# 06_SOM.net
KiCad netlist of a schematic drawn in Altium Designer
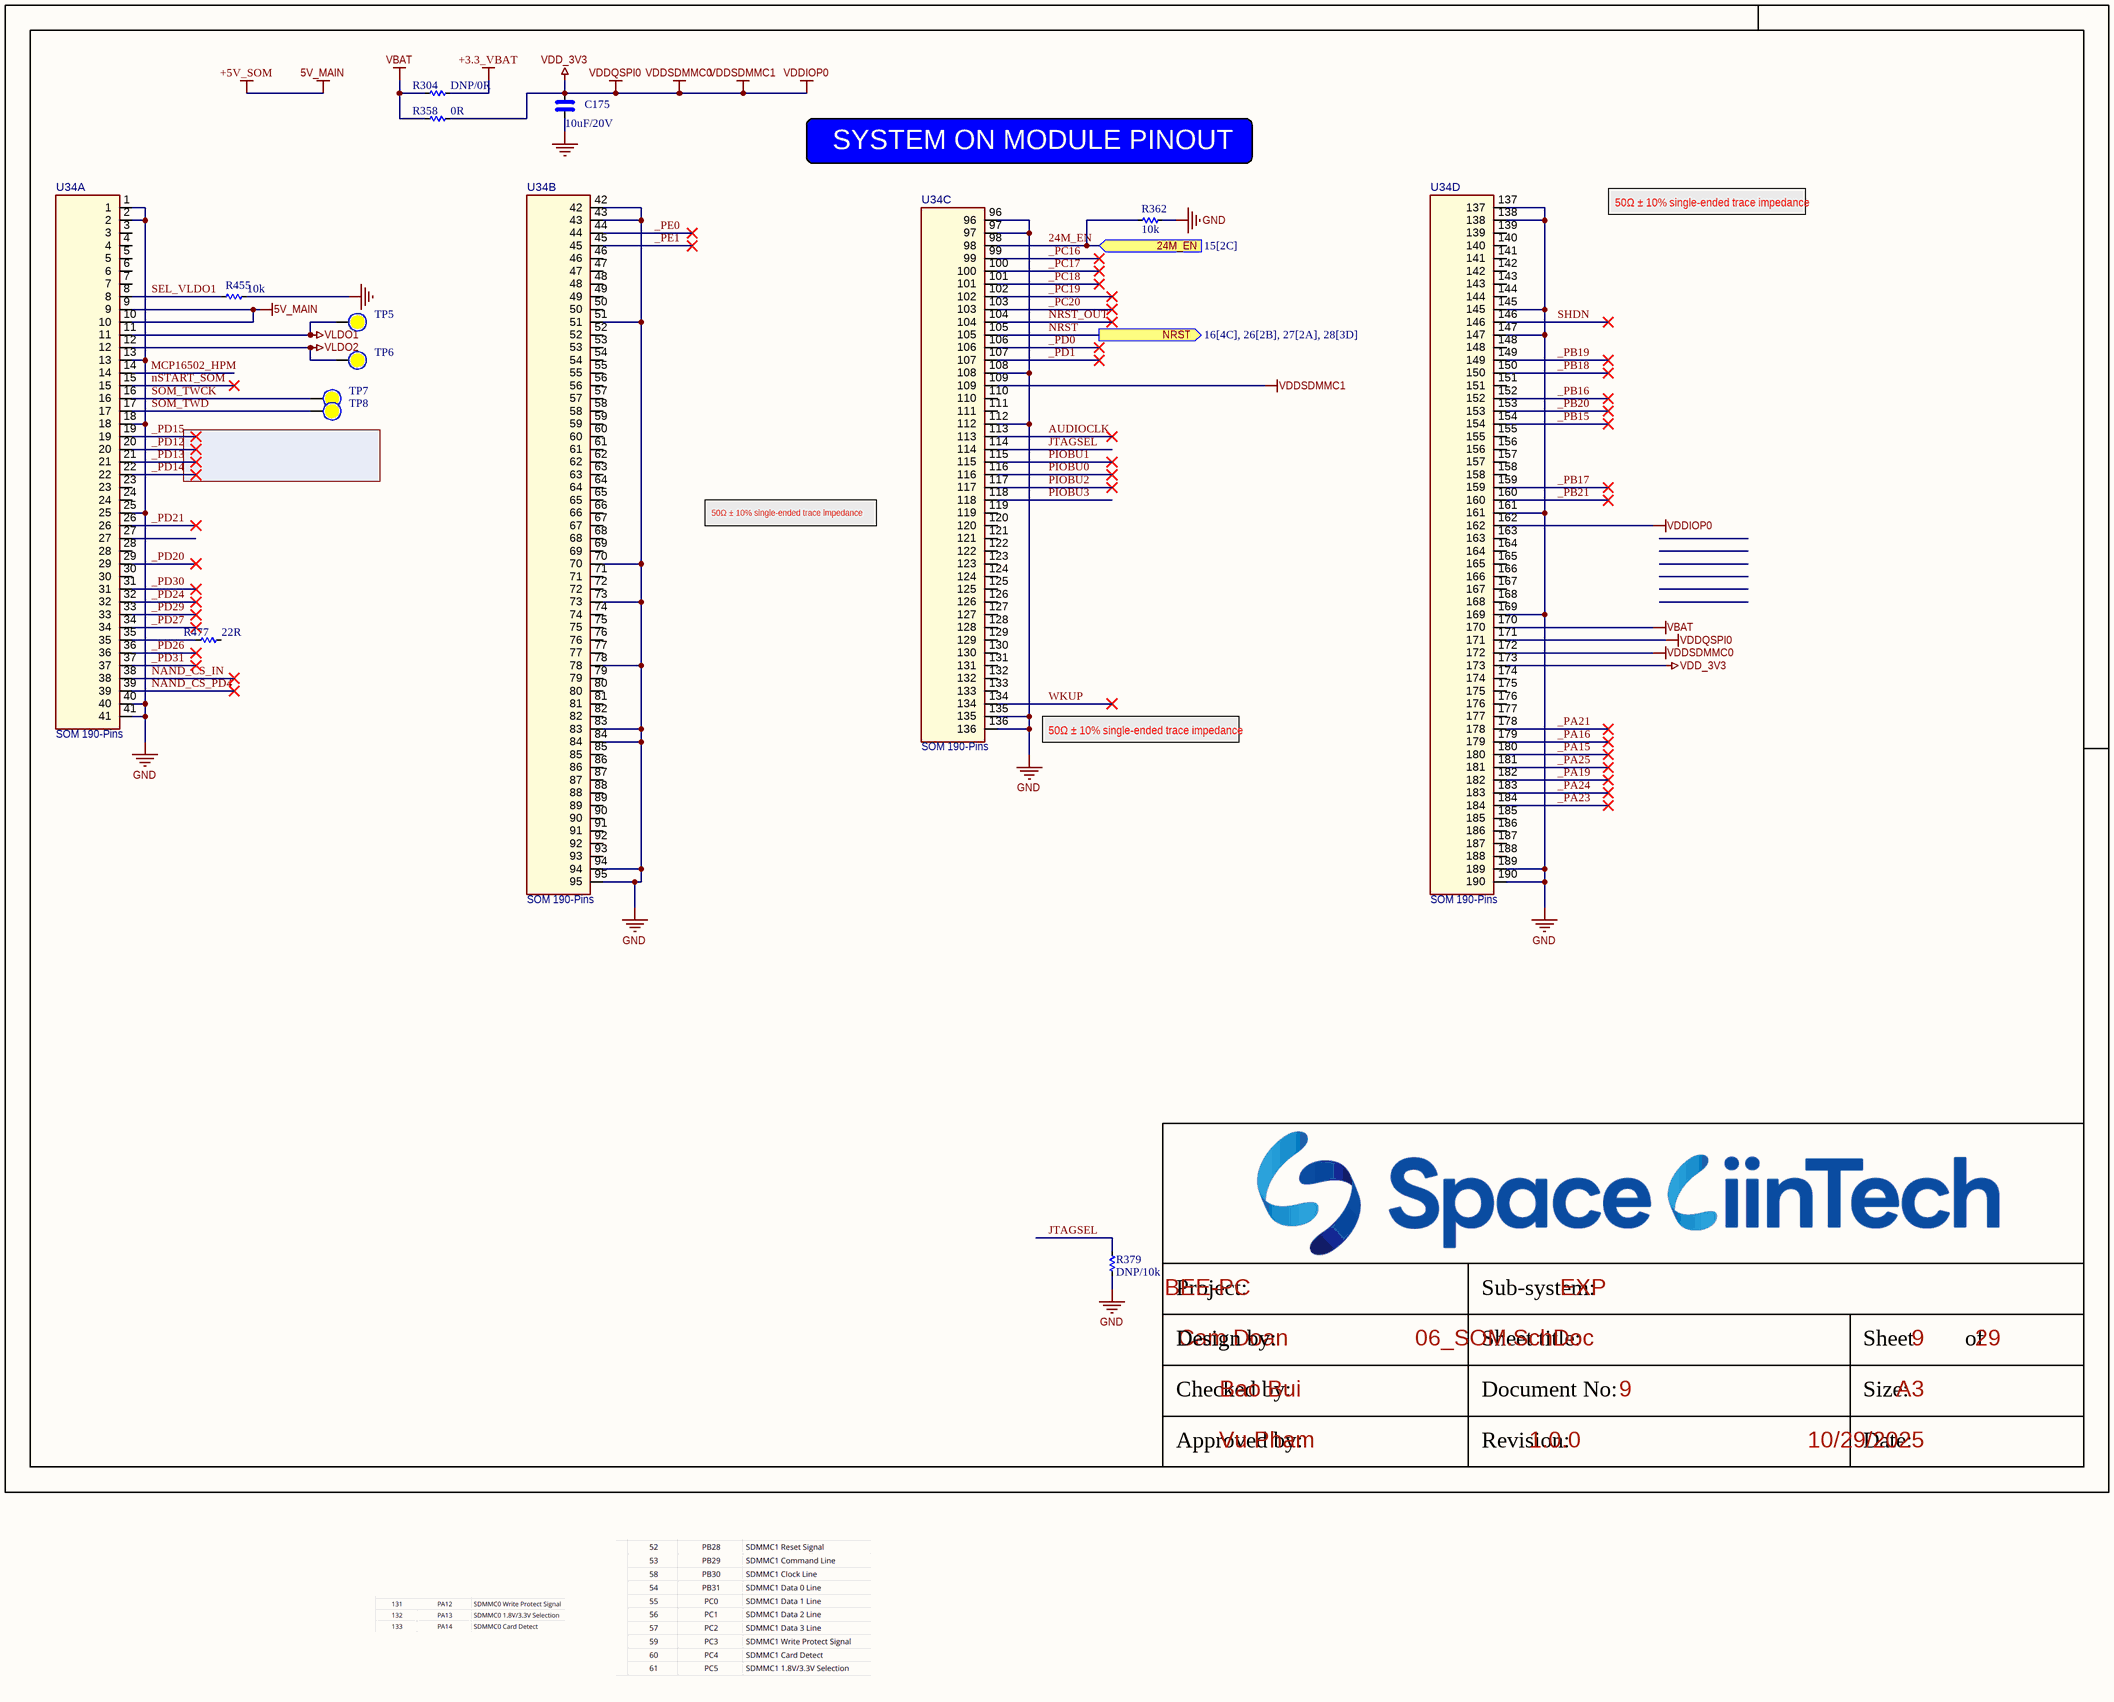
[diagram p0: 06_SOM.SchDoc]

(export (version "E")
  (design (tool "Eeschema 10.0.6"))
  (components
    (comp (ref "C175")
      (value "10uF/20V")
      (footprint "CAP_C_2012X110")
      (description "CAP CHIP High Value")
      (libsource (lib "LABLIB") (part "_CAP_C_High_2"))
    )
    (comp (ref "R304")
      (value "DNP/0R")
      (footprint "RES_C_1005X40")
      (description "RES")
      (libsource (lib "LABLIB") (part "_RES_B_2"))
    )
    (comp (ref "R358")
      (value "0R")
      (footprint "RES_C_1005X40")
      (description "RES")
      (libsource (lib "LABLIB") (part "_RES_B_2"))
    )
    (comp (ref "R362")
      (value "10k")
      (footprint "RES_C_1005X40")
      (description "RES")
      (libsource (lib "LABLIB") (part "_RES_B_2"))
    )
    (comp (ref "R379")
      (value "DNP/10k")
      (footprint "RES_C_1005X40")
      (description "RES")
      (libsource (lib "LABLIB") (part "_RES_B_2"))
    )
    (comp (ref "R455")
      (value "10k")
      (footprint "RES_C_1005X40")
      (description "RES")
      (libsource (lib "LABLIB") (part "_RES_B_2"))
    )
    (comp (ref "R477")
      (value "22R")
      (footprint "RES_C_1005X40")
      (description "RES")
      (libsource (lib "LABLIB") (part "_RES_B_2"))
    )
    (comp (ref "TP5")
      (value "~")
      (footprint "Testpoint_TH_D130H80")
      (description "Test Point")
      (libsource (lib "LABLIB") (part "Test Point"))
    )
    (comp (ref "TP6")
      (value "~")
      (footprint "Testpoint_TH_D130H80")
      (description "Test Point")
      (libsource (lib "LABLIB") (part "Test Point"))
    )
    (comp (ref "TP7")
      (value "~")
      (footprint "Testpoint_TH_D130H80")
      (description "Test Point")
      (libsource (lib "LABLIB") (part "Test Point"))
    )
    (comp (ref "TP8")
      (value "~")
      (footprint "Testpoint_TH_D130H80")
      (description "Test Point")
      (libsource (lib "LABLIB") (part "Test Point"))
    )
    (comp (ref "U34")
      (value "SOM 190-Pins")
      (footprint "SOM-38MMX30MM")
      (description "190-Castellated thru-holes, 38mm x 30mm package")
      (libsource (lib "SOM-190") (part "SOM-190"))
    )
  )
  (nets
    (net (code "1") (name "+3.3_VBAT") (class "Default")
      (node (ref "R304") (pin "1") (pinfunction "1_1") (pintype "passive"))
    )
    (net (code "2") (name "+5V_SOM") (class "Default")
      (node (ref "U34") (pin "10") (pinfunction "10_10") (pintype "passive"))
      (node (ref "U34") (pin "9") (pinfunction "9_9") (pintype "passive"))
    )
    (net (code "3") (name "/24M_EN") (class "Default")
      (node (ref "R362") (pin "2") (pinfunction "2_2") (pintype "passive"))
      (node (ref "U34") (pin "98") (pinfunction "98_98") (pintype "passive"))
    )
    (net (code "4") (name "/AUDIOCLK") (class "Default")
      (node (ref "U34") (pin "113") (pinfunction "113_113") (pintype "passive+no_connect"))
    )
    (net (code "5") (name "/JTAGSEL") (class "Default")
      (node (ref "R379") (pin "2") (pinfunction "2_2") (pintype "passive"))
      (node (ref "U34") (pin "114") (pinfunction "114_114") (pintype "passive"))
    )
    (net (code "6") (name "/MCP16502_HPM") (class "Default")
      (node (ref "U34") (pin "14") (pinfunction "14_14") (pintype "passive"))
    )
    (net (code "7") (name "/NAND_CS_IN") (class "Default")
      (node (ref "U34") (pin "38") (pinfunction "38_38") (pintype "passive+no_connect"))
    )
    (net (code "8") (name "/NAND_CS_PD4") (class "Default")
      (node (ref "U34") (pin "39") (pinfunction "39_39") (pintype "passive+no_connect"))
    )
    (net (code "9") (name "/NRST") (class "Default")
      (node (ref "U34") (pin "105") (pinfunction "105_105") (pintype "passive"))
    )
    (net (code "10") (name "/NRST_OUT") (class "Default")
      (node (ref "U34") (pin "104") (pinfunction "104_104") (pintype "passive+no_connect"))
    )
    (net (code "11") (name "/PIOBU0") (class "Default")
      (node (ref "U34") (pin "116") (pinfunction "116_116") (pintype "passive+no_connect"))
    )
    (net (code "12") (name "/PIOBU1") (class "Default")
      (node (ref "U34") (pin "115") (pinfunction "115_115") (pintype "passive+no_connect"))
    )
    (net (code "13") (name "/PIOBU2") (class "Default")
      (node (ref "U34") (pin "117") (pinfunction "117_117") (pintype "passive+no_connect"))
    )
    (net (code "14") (name "/PIOBU3") (class "Default")
      (node (ref "U34") (pin "118") (pinfunction "118_118") (pintype "passive"))
    )
    (net (code "15") (name "/SEL_VLDO1") (class "Default")
      (node (ref "R455") (pin "2") (pinfunction "2_2") (pintype "passive"))
      (node (ref "U34") (pin "8") (pinfunction "8_8") (pintype "passive"))
    )
    (net (code "16") (name "/SHDN") (class "Default")
      (node (ref "U34") (pin "146") (pinfunction "146_146") (pintype "passive+no_connect"))
    )
    (net (code "17") (name "/SOM_TWCK") (class "Default")
      (node (ref "TP7") (pin "0") (pinfunction "0_0") (pintype "passive"))
      (node (ref "U34") (pin "16") (pinfunction "16_16") (pintype "passive"))
    )
    (net (code "18") (name "/SOM_TWD") (class "Default")
      (node (ref "TP8") (pin "0") (pinfunction "0_0") (pintype "passive"))
      (node (ref "U34") (pin "17") (pinfunction "17_17") (pintype "passive"))
    )
    (net (code "19") (name "/WKUP") (class "Default")
      (node (ref "U34") (pin "134") (pinfunction "134_134") (pintype "passive+no_connect"))
    )
    (net (code "20") (name "/_PA15") (class "Default")
      (node (ref "U34") (pin "180") (pinfunction "180_180") (pintype "passive+no_connect"))
    )
    (net (code "21") (name "/_PA16") (class "Default")
      (node (ref "U34") (pin "179") (pinfunction "179_179") (pintype "passive+no_connect"))
    )
    (net (code "22") (name "/_PA19") (class "Default")
      (node (ref "U34") (pin "182") (pinfunction "182_182") (pintype "passive+no_connect"))
    )
    (net (code "23") (name "/_PA21") (class "Default")
      (node (ref "U34") (pin "178") (pinfunction "178_178") (pintype "passive+no_connect"))
    )
    (net (code "24") (name "/_PA23") (class "Default")
      (node (ref "U34") (pin "184") (pinfunction "184_184") (pintype "passive+no_connect"))
    )
    (net (code "25") (name "/_PA24") (class "Default")
      (node (ref "U34") (pin "183") (pinfunction "183_183") (pintype "passive+no_connect"))
    )
    (net (code "26") (name "/_PA25") (class "Default")
      (node (ref "U34") (pin "181") (pinfunction "181_181") (pintype "passive+no_connect"))
    )
    (net (code "27") (name "/_PB15") (class "Default")
      (node (ref "U34") (pin "154") (pinfunction "154_154") (pintype "passive+no_connect"))
    )
    (net (code "28") (name "/_PB16") (class "Default")
      (node (ref "U34") (pin "152") (pinfunction "152_152") (pintype "passive+no_connect"))
    )
    (net (code "29") (name "/_PB17") (class "Default")
      (node (ref "U34") (pin "159") (pinfunction "159_159") (pintype "passive+no_connect"))
    )
    (net (code "30") (name "/_PB18") (class "Default")
      (node (ref "U34") (pin "150") (pinfunction "150_150") (pintype "passive+no_connect"))
    )
    (net (code "31") (name "/_PB19") (class "Default")
      (node (ref "U34") (pin "149") (pinfunction "149_149") (pintype "passive+no_connect"))
    )
    (net (code "32") (name "/_PB20") (class "Default")
      (node (ref "U34") (pin "153") (pinfunction "153_153") (pintype "passive+no_connect"))
    )
    (net (code "33") (name "/_PB21") (class "Default")
      (node (ref "U34") (pin "160") (pinfunction "160_160") (pintype "passive+no_connect"))
    )
    (net (code "34") (name "/_PC16") (class "Default")
      (node (ref "U34") (pin "99") (pinfunction "99_99") (pintype "passive+no_connect"))
    )
    (net (code "35") (name "/_PC17") (class "Default")
      (node (ref "U34") (pin "100") (pinfunction "100_100") (pintype "passive+no_connect"))
    )
    (net (code "36") (name "/_PC18") (class "Default")
      (node (ref "U34") (pin "101") (pinfunction "101_101") (pintype "passive+no_connect"))
    )
    (net (code "37") (name "/_PC19") (class "Default")
      (node (ref "U34") (pin "102") (pinfunction "102_102") (pintype "passive+no_connect"))
    )
    (net (code "38") (name "/_PC20") (class "Default")
      (node (ref "U34") (pin "103") (pinfunction "103_103") (pintype "passive+no_connect"))
    )
    (net (code "39") (name "/_PD0") (class "Default")
      (node (ref "U34") (pin "106") (pinfunction "106_106") (pintype "passive+no_connect"))
    )
    (net (code "40") (name "/_PD1") (class "Default")
      (node (ref "U34") (pin "107") (pinfunction "107_107") (pintype "passive+no_connect"))
    )
    (net (code "41") (name "/_PD12") (class "Default")
      (node (ref "U34") (pin "20") (pinfunction "20_20") (pintype "passive+no_connect"))
    )
    (net (code "42") (name "/_PD13") (class "Default")
      (node (ref "U34") (pin "21") (pinfunction "21_21") (pintype "passive+no_connect"))
    )
    (net (code "43") (name "/_PD14") (class "Default")
      (node (ref "U34") (pin "22") (pinfunction "22_22") (pintype "passive+no_connect"))
    )
    (net (code "44") (name "/_PD15") (class "Default")
      (node (ref "U34") (pin "19") (pinfunction "19_19") (pintype "passive+no_connect"))
    )
    (net (code "45") (name "/_PD20") (class "Default")
      (node (ref "U34") (pin "29") (pinfunction "29_29") (pintype "passive+no_connect"))
    )
    (net (code "46") (name "/_PD21") (class "Default")
      (node (ref "U34") (pin "26") (pinfunction "26_26") (pintype "passive+no_connect"))
    )
    (net (code "47") (name "/_PD24") (class "Default")
      (node (ref "U34") (pin "32") (pinfunction "32_32") (pintype "passive+no_connect"))
    )
    (net (code "48") (name "/_PD26") (class "Default")
      (node (ref "U34") (pin "36") (pinfunction "36_36") (pintype "passive+no_connect"))
    )
    (net (code "49") (name "/_PD27") (class "Default")
      (node (ref "U34") (pin "34") (pinfunction "34_34") (pintype "passive+no_connect"))
    )
    (net (code "50") (name "/_PD29") (class "Default")
      (node (ref "U34") (pin "33") (pinfunction "33_33") (pintype "passive+no_connect"))
    )
    (net (code "51") (name "/_PD30") (class "Default")
      (node (ref "U34") (pin "31") (pinfunction "31_31") (pintype "passive+no_connect"))
    )
    (net (code "52") (name "/_PD31") (class "Default")
      (node (ref "U34") (pin "37") (pinfunction "37_37") (pintype "passive+no_connect"))
    )
    (net (code "53") (name "/_PE0") (class "Default")
      (node (ref "U34") (pin "44") (pinfunction "44_44") (pintype "passive+no_connect"))
    )
    (net (code "54") (name "/_PE1") (class "Default")
      (node (ref "U34") (pin "45") (pinfunction "45_45") (pintype "passive+no_connect"))
    )
    (net (code "55") (name "/nSTART_SOM") (class "Default")
      (node (ref "U34") (pin "15") (pinfunction "15_15") (pintype "passive+no_connect"))
    )
    (net (code "56") (name "GND") (class "Default")
      (node (ref "C175") (pin "2") (pinfunction "2_2") (pintype "passive"))
      (node (ref "R362") (pin "1") (pinfunction "1_1") (pintype "passive"))
      (node (ref "R379") (pin "1") (pinfunction "1_1") (pintype "passive"))
      (node (ref "R455") (pin "1") (pinfunction "1_1") (pintype "passive"))
      (node (ref "U34") (pin "1") (pinfunction "1_1") (pintype "passive"))
      (node (ref "U34") (pin "108") (pinfunction "108_108") (pintype "passive"))
      (node (ref "U34") (pin "112") (pinfunction "112_112") (pintype "passive"))
      (node (ref "U34") (pin "13") (pinfunction "13_13") (pintype "passive"))
      (node (ref "U34") (pin "135") (pinfunction "135_135") (pintype "passive"))
      (node (ref "U34") (pin "136") (pinfunction "136_136") (pintype "passive"))
      (node (ref "U34") (pin "137") (pinfunction "137_137") (pintype "passive"))
      (node (ref "U34") (pin "138") (pinfunction "138_138") (pintype "passive"))
      (node (ref "U34") (pin "145") (pinfunction "145_145") (pintype "passive"))
      (node (ref "U34") (pin "147") (pinfunction "147_147") (pintype "passive"))
      (node (ref "U34") (pin "161") (pinfunction "161_161") (pintype "passive"))
      (node (ref "U34") (pin "169") (pinfunction "169_169") (pintype "passive"))
      (node (ref "U34") (pin "18") (pinfunction "18_18") (pintype "passive"))
      (node (ref "U34") (pin "189") (pinfunction "189_189") (pintype "passive"))
      (node (ref "U34") (pin "190") (pinfunction "190_190") (pintype "passive"))
      (node (ref "U34") (pin "2") (pinfunction "2_2") (pintype "passive"))
      (node (ref "U34") (pin "25") (pinfunction "25_25") (pintype "passive"))
      (node (ref "U34") (pin "40") (pinfunction "40_40") (pintype "passive"))
      (node (ref "U34") (pin "41") (pinfunction "41_41") (pintype "passive"))
      (node (ref "U34") (pin "42") (pinfunction "42_42") (pintype "passive"))
      (node (ref "U34") (pin "43") (pinfunction "43_43") (pintype "passive"))
      (node (ref "U34") (pin "51") (pinfunction "51_51") (pintype "passive"))
      (node (ref "U34") (pin "70") (pinfunction "70_70") (pintype "passive"))
      (node (ref "U34") (pin "73") (pinfunction "73_73") (pintype "passive"))
      (node (ref "U34") (pin "78") (pinfunction "78_78") (pintype "passive"))
      (node (ref "U34") (pin "83") (pinfunction "83_83") (pintype "passive"))
      (node (ref "U34") (pin "84") (pinfunction "84_84") (pintype "passive"))
      (node (ref "U34") (pin "94") (pinfunction "94_94") (pintype "passive"))
      (node (ref "U34") (pin "95") (pinfunction "95_95") (pintype "passive"))
      (node (ref "U34") (pin "96") (pinfunction "96_96") (pintype "passive"))
      (node (ref "U34") (pin "97") (pinfunction "97_97") (pintype "passive"))
    )
    (net (code "57") (name "Net-(R477-Pad2)") (class "Default")
      (node (ref "R477") (pin "2") (pinfunction "2_2") (pintype "passive"))
      (node (ref "U34") (pin "35") (pinfunction "35_35") (pintype "passive"))
    )
    (net (code "58") (name "VBAT") (class "Default")
      (node (ref "R304") (pin "2") (pinfunction "2_2") (pintype "passive"))
      (node (ref "R358") (pin "2") (pinfunction "2_2") (pintype "passive"))
      (node (ref "U34") (pin "170") (pinfunction "170_170") (pintype "passive"))
    )
    (net (code "59") (name "VDDIOP0") (class "Default")
      (node (ref "C175") (pin "1") (pinfunction "1_1") (pintype "passive"))
      (node (ref "R358") (pin "1") (pinfunction "1_1") (pintype "passive"))
      (node (ref "U34") (pin "109") (pinfunction "109_109") (pintype "passive"))
      (node (ref "U34") (pin "162") (pinfunction "162_162") (pintype "passive"))
      (node (ref "U34") (pin "171") (pinfunction "171_171") (pintype "passive"))
      (node (ref "U34") (pin "172") (pinfunction "172_172") (pintype "passive"))
      (node (ref "U34") (pin "173") (pinfunction "173_173") (pintype "passive"))
    )
    (net (code "60") (name "VLDO1") (class "Default")
      (node (ref "TP5") (pin "0") (pinfunction "0_0") (pintype "passive"))
      (node (ref "U34") (pin "11") (pinfunction "11_11") (pintype "passive"))
    )
    (net (code "61") (name "VLDO2") (class "Default")
      (node (ref "TP6") (pin "0") (pinfunction "0_0") (pintype "passive"))
      (node (ref "U34") (pin "12") (pinfunction "12_12") (pintype "passive"))
    )
    (net (code "62") (name "unconnected-(R477-Pad1)") (class "Default")
      (node (ref "R477") (pin "1") (pinfunction "1_1") (pintype "passive"))
    )
    (net (code "63") (name "unconnected-(U34-Pad3)") (class "Default")
      (node (ref "U34") (pin "3") (pinfunction "3_3") (pintype "passive"))
    )
    (net (code "64") (name "unconnected-(U34-Pad4)") (class "Default")
      (node (ref "U34") (pin "4") (pinfunction "4_4") (pintype "passive"))
    )
    (net (code "65") (name "unconnected-(U34-Pad5)") (class "Default")
      (node (ref "U34") (pin "5") (pinfunction "5_5") (pintype "passive"))
    )
    (net (code "66") (name "unconnected-(U34-Pad6)") (class "Default")
      (node (ref "U34") (pin "6") (pinfunction "6_6") (pintype "passive"))
    )
    (net (code "67") (name "unconnected-(U34-Pad7)") (class "Default")
      (node (ref "U34") (pin "7") (pinfunction "7_7") (pintype "passive"))
    )
    (net (code "68") (name "unconnected-(U34-Pad23)") (class "Default")
      (node (ref "U34") (pin "23") (pinfunction "23_23") (pintype "passive"))
    )
    (net (code "69") (name "unconnected-(U34-Pad24)") (class "Default")
      (node (ref "U34") (pin "24") (pinfunction "24_24") (pintype "passive"))
    )
    (net (code "70") (name "unconnected-(U34-Pad27)") (class "Default")
      (node (ref "U34") (pin "27") (pinfunction "27_27") (pintype "passive"))
    )
    (net (code "71") (name "unconnected-(U34-Pad28)") (class "Default")
      (node (ref "U34") (pin "28") (pinfunction "28_28") (pintype "passive"))
    )
    (net (code "72") (name "unconnected-(U34-Pad30)") (class "Default")
      (node (ref "U34") (pin "30") (pinfunction "30_30") (pintype "passive"))
    )
    (net (code "73") (name "unconnected-(U34-Pad46)") (class "Default")
      (node (ref "U34") (pin "46") (pinfunction "46_46") (pintype "passive"))
    )
    (net (code "74") (name "unconnected-(U34-Pad47)") (class "Default")
      (node (ref "U34") (pin "47") (pinfunction "47_47") (pintype "passive"))
    )
    (net (code "75") (name "unconnected-(U34-Pad48)") (class "Default")
      (node (ref "U34") (pin "48") (pinfunction "48_48") (pintype "passive"))
    )
    (net (code "76") (name "unconnected-(U34-Pad49)") (class "Default")
      (node (ref "U34") (pin "49") (pinfunction "49_49") (pintype "passive"))
    )
    (net (code "77") (name "unconnected-(U34-Pad50)") (class "Default")
      (node (ref "U34") (pin "50") (pinfunction "50_50") (pintype "passive"))
    )
    (net (code "78") (name "unconnected-(U34-Pad52)") (class "Default")
      (node (ref "U34") (pin "52") (pinfunction "52_52") (pintype "passive"))
    )
    (net (code "79") (name "unconnected-(U34-Pad53)") (class "Default")
      (node (ref "U34") (pin "53") (pinfunction "53_53") (pintype "passive"))
    )
    (net (code "80") (name "unconnected-(U34-Pad54)") (class "Default")
      (node (ref "U34") (pin "54") (pinfunction "54_54") (pintype "passive"))
    )
    (net (code "81") (name "unconnected-(U34-Pad55)") (class "Default")
      (node (ref "U34") (pin "55") (pinfunction "55_55") (pintype "passive"))
    )
    (net (code "82") (name "unconnected-(U34-Pad56)") (class "Default")
      (node (ref "U34") (pin "56") (pinfunction "56_56") (pintype "passive"))
    )
    (net (code "83") (name "unconnected-(U34-Pad57)") (class "Default")
      (node (ref "U34") (pin "57") (pinfunction "57_57") (pintype "passive"))
    )
    (net (code "84") (name "unconnected-(U34-Pad58)") (class "Default")
      (node (ref "U34") (pin "58") (pinfunction "58_58") (pintype "passive"))
    )
    (net (code "85") (name "unconnected-(U34-Pad59)") (class "Default")
      (node (ref "U34") (pin "59") (pinfunction "59_59") (pintype "passive"))
    )
    (net (code "86") (name "unconnected-(U34-Pad60)") (class "Default")
      (node (ref "U34") (pin "60") (pinfunction "60_60") (pintype "passive"))
    )
    (net (code "87") (name "unconnected-(U34-Pad61)") (class "Default")
      (node (ref "U34") (pin "61") (pinfunction "61_61") (pintype "passive"))
    )
    (net (code "88") (name "unconnected-(U34-Pad62)") (class "Default")
      (node (ref "U34") (pin "62") (pinfunction "62_62") (pintype "passive"))
    )
    (net (code "89") (name "unconnected-(U34-Pad63)") (class "Default")
      (node (ref "U34") (pin "63") (pinfunction "63_63") (pintype "passive"))
    )
    (net (code "90") (name "unconnected-(U34-Pad64)") (class "Default")
      (node (ref "U34") (pin "64") (pinfunction "64_64") (pintype "passive"))
    )
    (net (code "91") (name "unconnected-(U34-Pad65)") (class "Default")
      (node (ref "U34") (pin "65") (pinfunction "65_65") (pintype "passive"))
    )
    (net (code "92") (name "unconnected-(U34-Pad66)") (class "Default")
      (node (ref "U34") (pin "66") (pinfunction "66_66") (pintype "passive"))
    )
    (net (code "93") (name "unconnected-(U34-Pad67)") (class "Default")
      (node (ref "U34") (pin "67") (pinfunction "67_67") (pintype "passive"))
    )
    (net (code "94") (name "unconnected-(U34-Pad68)") (class "Default")
      (node (ref "U34") (pin "68") (pinfunction "68_68") (pintype "passive"))
    )
    (net (code "95") (name "unconnected-(U34-Pad69)") (class "Default")
      (node (ref "U34") (pin "69") (pinfunction "69_69") (pintype "passive"))
    )
    (net (code "96") (name "unconnected-(U34-Pad71)") (class "Default")
      (node (ref "U34") (pin "71") (pinfunction "71_71") (pintype "passive"))
    )
    (net (code "97") (name "unconnected-(U34-Pad72)") (class "Default")
      (node (ref "U34") (pin "72") (pinfunction "72_72") (pintype "passive"))
    )
    (net (code "98") (name "unconnected-(U34-Pad74)") (class "Default")
      (node (ref "U34") (pin "74") (pinfunction "74_74") (pintype "passive"))
    )
    (net (code "99") (name "unconnected-(U34-Pad75)") (class "Default")
      (node (ref "U34") (pin "75") (pinfunction "75_75") (pintype "passive"))
    )
    (net (code "100") (name "unconnected-(U34-Pad76)") (class "Default")
      (node (ref "U34") (pin "76") (pinfunction "76_76") (pintype "passive"))
    )
    (net (code "101") (name "unconnected-(U34-Pad77)") (class "Default")
      (node (ref "U34") (pin "77") (pinfunction "77_77") (pintype "passive"))
    )
    (net (code "102") (name "unconnected-(U34-Pad79)") (class "Default")
      (node (ref "U34") (pin "79") (pinfunction "79_79") (pintype "passive"))
    )
    (net (code "103") (name "unconnected-(U34-Pad80)") (class "Default")
      (node (ref "U34") (pin "80") (pinfunction "80_80") (pintype "passive"))
    )
    (net (code "104") (name "unconnected-(U34-Pad81)") (class "Default")
      (node (ref "U34") (pin "81") (pinfunction "81_81") (pintype "passive"))
    )
    (net (code "105") (name "unconnected-(U34-Pad82)") (class "Default")
      (node (ref "U34") (pin "82") (pinfunction "82_82") (pintype "passive"))
    )
    (net (code "106") (name "unconnected-(U34-Pad85)") (class "Default")
      (node (ref "U34") (pin "85") (pinfunction "85_85") (pintype "passive"))
    )
    (net (code "107") (name "unconnected-(U34-Pad86)") (class "Default")
      (node (ref "U34") (pin "86") (pinfunction "86_86") (pintype "passive"))
    )
    (net (code "108") (name "unconnected-(U34-Pad87)") (class "Default")
      (node (ref "U34") (pin "87") (pinfunction "87_87") (pintype "passive"))
    )
    (net (code "109") (name "unconnected-(U34-Pad88)") (class "Default")
      (node (ref "U34") (pin "88") (pinfunction "88_88") (pintype "passive"))
    )
    (net (code "110") (name "unconnected-(U34-Pad89)") (class "Default")
      (node (ref "U34") (pin "89") (pinfunction "89_89") (pintype "passive"))
    )
    (net (code "111") (name "unconnected-(U34-Pad90)") (class "Default")
      (node (ref "U34") (pin "90") (pinfunction "90_90") (pintype "passive"))
    )
    (net (code "112") (name "unconnected-(U34-Pad91)") (class "Default")
      (node (ref "U34") (pin "91") (pinfunction "91_91") (pintype "passive"))
    )
    (net (code "113") (name "unconnected-(U34-Pad92)") (class "Default")
      (node (ref "U34") (pin "92") (pinfunction "92_92") (pintype "passive"))
    )
    (net (code "114") (name "unconnected-(U34-Pad93)") (class "Default")
      (node (ref "U34") (pin "93") (pinfunction "93_93") (pintype "passive"))
    )
    (net (code "115") (name "unconnected-(U34-Pad110)") (class "Default")
      (node (ref "U34") (pin "110") (pinfunction "110_110") (pintype "passive"))
    )
    (net (code "116") (name "unconnected-(U34-Pad111)") (class "Default")
      (node (ref "U34") (pin "111") (pinfunction "111_111") (pintype "passive"))
    )
    (net (code "117") (name "unconnected-(U34-Pad119)") (class "Default")
      (node (ref "U34") (pin "119") (pinfunction "119_119") (pintype "passive"))
    )
    (net (code "118") (name "unconnected-(U34-Pad120)") (class "Default")
      (node (ref "U34") (pin "120") (pinfunction "120_120") (pintype "passive"))
    )
    (net (code "119") (name "unconnected-(U34-Pad121)") (class "Default")
      (node (ref "U34") (pin "121") (pinfunction "121_121") (pintype "passive"))
    )
    (net (code "120") (name "unconnected-(U34-Pad122)") (class "Default")
      (node (ref "U34") (pin "122") (pinfunction "122_122") (pintype "passive"))
    )
    (net (code "121") (name "unconnected-(U34-Pad123)") (class "Default")
      (node (ref "U34") (pin "123") (pinfunction "123_123") (pintype "passive"))
    )
    (net (code "122") (name "unconnected-(U34-Pad124)") (class "Default")
      (node (ref "U34") (pin "124") (pinfunction "124_124") (pintype "passive"))
    )
    (net (code "123") (name "unconnected-(U34-Pad125)") (class "Default")
      (node (ref "U34") (pin "125") (pinfunction "125_125") (pintype "passive"))
    )
    (net (code "124") (name "unconnected-(U34-Pad126)") (class "Default")
      (node (ref "U34") (pin "126") (pinfunction "126_126") (pintype "passive"))
    )
    (net (code "125") (name "unconnected-(U34-Pad127)") (class "Default")
      (node (ref "U34") (pin "127") (pinfunction "127_127") (pintype "passive"))
    )
    (net (code "126") (name "unconnected-(U34-Pad128)") (class "Default")
      (node (ref "U34") (pin "128") (pinfunction "128_128") (pintype "passive"))
    )
    (net (code "127") (name "unconnected-(U34-Pad129)") (class "Default")
      (node (ref "U34") (pin "129") (pinfunction "129_129") (pintype "passive"))
    )
    (net (code "128") (name "unconnected-(U34-Pad130)") (class "Default")
      (node (ref "U34") (pin "130") (pinfunction "130_130") (pintype "passive"))
    )
    (net (code "129") (name "unconnected-(U34-Pad131)") (class "Default")
      (node (ref "U34") (pin "131") (pinfunction "131_131") (pintype "passive"))
    )
    (net (code "130") (name "unconnected-(U34-Pad132)") (class "Default")
      (node (ref "U34") (pin "132") (pinfunction "132_132") (pintype "passive"))
    )
    (net (code "131") (name "unconnected-(U34-Pad133)") (class "Default")
      (node (ref "U34") (pin "133") (pinfunction "133_133") (pintype "passive"))
    )
    (net (code "132") (name "unconnected-(U34-Pad139)") (class "Default")
      (node (ref "U34") (pin "139") (pinfunction "139_139") (pintype "passive"))
    )
    (net (code "133") (name "unconnected-(U34-Pad140)") (class "Default")
      (node (ref "U34") (pin "140") (pinfunction "140_140") (pintype "passive"))
    )
    (net (code "134") (name "unconnected-(U34-Pad141)") (class "Default")
      (node (ref "U34") (pin "141") (pinfunction "141_141") (pintype "passive"))
    )
    (net (code "135") (name "unconnected-(U34-Pad142)") (class "Default")
      (node (ref "U34") (pin "142") (pinfunction "142_142") (pintype "passive"))
    )
    (net (code "136") (name "unconnected-(U34-Pad143)") (class "Default")
      (node (ref "U34") (pin "143") (pinfunction "143_143") (pintype "passive"))
    )
    (net (code "137") (name "unconnected-(U34-Pad144)") (class "Default")
      (node (ref "U34") (pin "144") (pinfunction "144_144") (pintype "passive"))
    )
    (net (code "138") (name "unconnected-(U34-Pad148)") (class "Default")
      (node (ref "U34") (pin "148") (pinfunction "148_148") (pintype "passive"))
    )
    (net (code "139") (name "unconnected-(U34-Pad151)") (class "Default")
      (node (ref "U34") (pin "151") (pinfunction "151_151") (pintype "passive"))
    )
    (net (code "140") (name "unconnected-(U34-Pad155)") (class "Default")
      (node (ref "U34") (pin "155") (pinfunction "155_155") (pintype "passive"))
    )
    (net (code "141") (name "unconnected-(U34-Pad156)") (class "Default")
      (node (ref "U34") (pin "156") (pinfunction "156_156") (pintype "passive"))
    )
    (net (code "142") (name "unconnected-(U34-Pad157)") (class "Default")
      (node (ref "U34") (pin "157") (pinfunction "157_157") (pintype "passive"))
    )
    (net (code "143") (name "unconnected-(U34-Pad158)") (class "Default")
      (node (ref "U34") (pin "158") (pinfunction "158_158") (pintype "passive"))
    )
    (net (code "144") (name "unconnected-(U34-Pad163)") (class "Default")
      (node (ref "U34") (pin "163") (pinfunction "163_163") (pintype "passive"))
    )
    (net (code "145") (name "unconnected-(U34-Pad164)") (class "Default")
      (node (ref "U34") (pin "164") (pinfunction "164_164") (pintype "passive"))
    )
    (net (code "146") (name "unconnected-(U34-Pad165)") (class "Default")
      (node (ref "U34") (pin "165") (pinfunction "165_165") (pintype "passive"))
    )
    (net (code "147") (name "unconnected-(U34-Pad166)") (class "Default")
      (node (ref "U34") (pin "166") (pinfunction "166_166") (pintype "passive"))
    )
    (net (code "148") (name "unconnected-(U34-Pad167)") (class "Default")
      (node (ref "U34") (pin "167") (pinfunction "167_167") (pintype "passive"))
    )
    (net (code "149") (name "unconnected-(U34-Pad168)") (class "Default")
      (node (ref "U34") (pin "168") (pinfunction "168_168") (pintype "passive"))
    )
    (net (code "150") (name "unconnected-(U34-Pad174)") (class "Default")
      (node (ref "U34") (pin "174") (pinfunction "174_174") (pintype "passive"))
    )
    (net (code "151") (name "unconnected-(U34-Pad175)") (class "Default")
      (node (ref "U34") (pin "175") (pinfunction "175_175") (pintype "passive"))
    )
    (net (code "152") (name "unconnected-(U34-Pad176)") (class "Default")
      (node (ref "U34") (pin "176") (pinfunction "176_176") (pintype "passive"))
    )
    (net (code "153") (name "unconnected-(U34-Pad177)") (class "Default")
      (node (ref "U34") (pin "177") (pinfunction "177_177") (pintype "passive"))
    )
    (net (code "154") (name "unconnected-(U34-Pad185)") (class "Default")
      (node (ref "U34") (pin "185") (pinfunction "185_185") (pintype "passive"))
    )
    (net (code "155") (name "unconnected-(U34-Pad186)") (class "Default")
      (node (ref "U34") (pin "186") (pinfunction "186_186") (pintype "passive"))
    )
    (net (code "156") (name "unconnected-(U34-Pad187)") (class "Default")
      (node (ref "U34") (pin "187") (pinfunction "187_187") (pintype "passive"))
    )
    (net (code "157") (name "unconnected-(U34-Pad188)") (class "Default")
      (node (ref "U34") (pin "188") (pinfunction "188_188") (pintype "passive"))
    )
  )
)
